# Adafruit_2_2_SPI_240x320.net
KiCad netlist of a schematic drawn in EAGLE
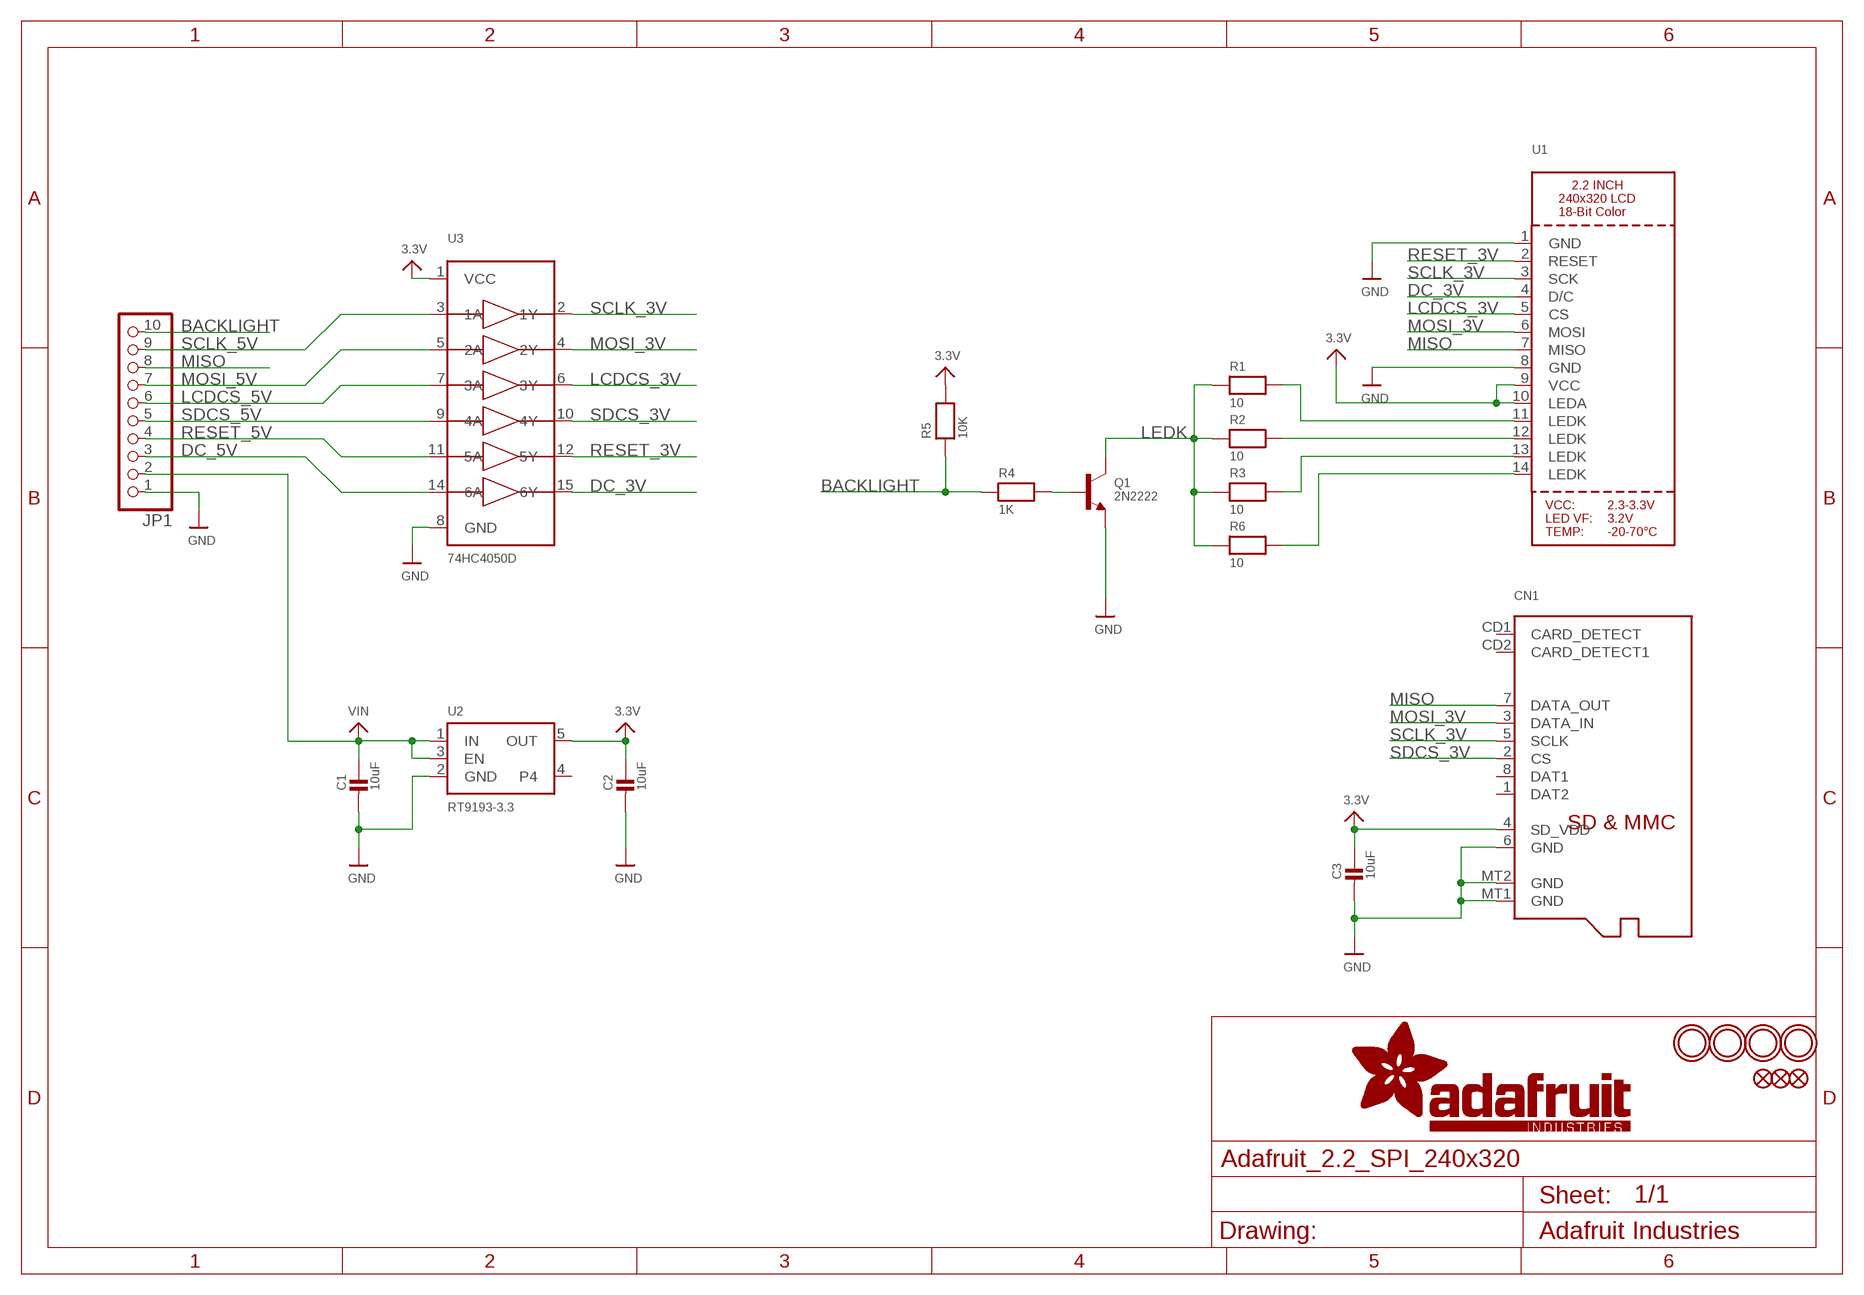
[diagram p0: schematic, sheet 1]

(export (version "E")
  (design (tool "Eeschema 10.0.6"))
  (components
    (comp (ref "C1")
      (value "10uF")
      (footprint "eagle-import:_0805MP")
      (libsource (lib "eagle-import") (part "CAP_CERAMIC_0805MP"))
    )
    (comp (ref "C2")
      (value "10uF")
      (footprint "eagle-import:_0805MP")
      (libsource (lib "eagle-import") (part "CAP_CERAMIC_0805MP"))
    )
    (comp (ref "C3")
      (value "10uF")
      (footprint "eagle-import:_0805MP")
      (libsource (lib "eagle-import") (part "CAP_CERAMIC_0805MP"))
    )
    (comp (ref "CN1")
      (value "MICROSD")
      (footprint "eagle-import:MICROSD")
      (libsource (lib "eagle-import") (part "MICROSD"))
    )
    (comp (ref "FID1")
      (value "FIDUCIAL\"\"")
      (footprint "eagle-import:FIDUCIAL_1MM")
      (libsource (lib "eagle-import") (part "FIDUCIAL{dblquote}{dblquote}"))
    )
    (comp (ref "FID2")
      (value "FIDUCIAL\"\"")
      (footprint "eagle-import:FIDUCIAL_1MM")
      (libsource (lib "eagle-import") (part "FIDUCIAL{dblquote}{dblquote}"))
    )
    (comp (ref "FID3")
      (value "FIDUCIAL\"\"")
      (footprint "eagle-import:FIDUCIAL_1MM")
      (fields (field (name "BOM") "EXCLUDE"))
      (libsource (lib "eagle-import") (part "FIDUCIAL{dblquote}{dblquote}"))
    )
    (comp (ref "JP1")
      (value "HEADER-1X1070MIL")
      (footprint "eagle-import:1X10_ROUND70")
      (libsource (lib "eagle-import") (part "HEADER-1X1070MIL"))
    )
    (comp (ref "Q1")
      (value "2N2222")
      (footprint "eagle-import:SOT23-WIDE")
      (libsource (lib "eagle-import") (part "TRANSISTOR_NPNWIDE"))
    )
    (comp (ref "R1")
      (value "10")
      (footprint "eagle-import:_0805MP")
      (libsource (lib "eagle-import") (part "RESISTOR_0805MP"))
    )
    (comp (ref "R2")
      (value "10")
      (footprint "eagle-import:_0805MP")
      (libsource (lib "eagle-import") (part "RESISTOR_0805MP"))
    )
    (comp (ref "R3")
      (value "10")
      (footprint "eagle-import:_0805MP")
      (libsource (lib "eagle-import") (part "RESISTOR_0805MP"))
    )
    (comp (ref "R4")
      (value "1K")
      (footprint "eagle-import:_0805MP")
      (libsource (lib "eagle-import") (part "RESISTOR_0805MP"))
    )
    (comp (ref "R5")
      (value "10K")
      (footprint "eagle-import:_0805MP")
      (libsource (lib "eagle-import") (part "RESISTOR_0805MP"))
    )
    (comp (ref "R6")
      (value "10")
      (footprint "eagle-import:_0805MP")
      (libsource (lib "eagle-import") (part "RESISTOR_0805MP"))
    )
    (comp (ref "U$2")
      (value "MOUNTINGHOLE2.5")
      (footprint "eagle-import:MOUNTINGHOLE_2.5_PLATED")
      (libsource (lib "eagle-import") (part "MOUNTINGHOLE2.5"))
    )
    (comp (ref "U$3")
      (value "MOUNTINGHOLE2.5")
      (footprint "eagle-import:MOUNTINGHOLE_2.5_PLATED")
      (libsource (lib "eagle-import") (part "MOUNTINGHOLE2.5"))
    )
    (comp (ref "U$4")
      (value "MOUNTINGHOLE2.5")
      (footprint "eagle-import:MOUNTINGHOLE_2.5_PLATED")
      (libsource (lib "eagle-import") (part "MOUNTINGHOLE2.5"))
    )
    (comp (ref "U$5")
      (value "MOUNTINGHOLE2.5")
      (footprint "eagle-import:MOUNTINGHOLE_2.5_PLATED")
      (libsource (lib "eagle-import") (part "MOUNTINGHOLE2.5"))
    )
    (comp (ref "U1")
      (value "DISP_LCD_TM022HDH26")
      (footprint "eagle-import:TM022HDH26_2.2IN_LCD")
      (libsource (lib "eagle-import") (part "DISP_LCD_TM022HDH26"))
    )
    (comp (ref "U2")
      (value "RT9193-3.3")
      (footprint "eagle-import:SOT23-5")
      (libsource (lib "eagle-import") (part "VREG_SOT23-5"))
    )
    (comp (ref "U3")
      (value "74HC4050D")
      (footprint "eagle-import:SOIC16")
      (libsource (lib "eagle-import") (part "74HC4050D"))
    )
  )
  (nets
    (net (code "1") (name "/BACKLIGHT") (class "Default")
      (node (ref "JP1") (pin "10") (pinfunction "10_10") (pintype "passive"))
      (node (ref "R4") (pin "1") (pinfunction "1_1") (pintype "passive"))
      (node (ref "R5") (pin "1") (pinfunction "1_1") (pintype "passive"))
    )
    (net (code "2") (name "/DC_3V") (class "Default")
      (node (ref "U1") (pin "4") (pinfunction "D/C_4") (pintype "input"))
      (node (ref "U3") (pin "15") (pinfunction "6Y_15") (pintype "bidirectional"))
    )
    (net (code "3") (name "/DC_5V") (class "Default")
      (node (ref "JP1") (pin "3") (pinfunction "3_3") (pintype "passive"))
      (node (ref "U3") (pin "14") (pinfunction "6A_14") (pintype "bidirectional"))
    )
    (net (code "4") (name "/LCDCS_3V") (class "Default")
      (node (ref "U1") (pin "5") (pinfunction "CS_5") (pintype "input"))
      (node (ref "U3") (pin "6") (pinfunction "3Y_6") (pintype "bidirectional"))
    )
    (net (code "5") (name "/LCDCS_5V") (class "Default")
      (node (ref "JP1") (pin "6") (pinfunction "6_6") (pintype "passive"))
      (node (ref "U3") (pin "7") (pinfunction "3A_7") (pintype "bidirectional"))
    )
    (net (code "6") (name "/LEDK") (class "Default")
      (node (ref "Q1") (pin "3") (pinfunction "C_3") (pintype "passive"))
      (node (ref "R1") (pin "1") (pinfunction "1_1") (pintype "passive"))
      (node (ref "R2") (pin "1") (pinfunction "1_1") (pintype "passive"))
      (node (ref "R3") (pin "1") (pinfunction "1_1") (pintype "passive"))
      (node (ref "R6") (pin "1") (pinfunction "1_1") (pintype "passive"))
    )
    (net (code "7") (name "/MISO") (class "Default")
      (node (ref "CN1") (pin "7") (pinfunction "DATA_OUT_7") (pintype "output"))
      (node (ref "JP1") (pin "8") (pinfunction "8_8") (pintype "passive"))
      (node (ref "U1") (pin "7") (pinfunction "MISO_7") (pintype "output"))
    )
    (net (code "8") (name "/MOSI_3V") (class "Default")
      (node (ref "CN1") (pin "3") (pinfunction "DATA_IN_3") (pintype "input"))
      (node (ref "U1") (pin "6") (pinfunction "MOSI_6") (pintype "input"))
      (node (ref "U3") (pin "4") (pinfunction "2Y_4") (pintype "bidirectional"))
    )
    (net (code "9") (name "/MOSI_5V") (class "Default")
      (node (ref "JP1") (pin "7") (pinfunction "7_7") (pintype "passive"))
      (node (ref "U3") (pin "5") (pinfunction "2A_5") (pintype "bidirectional"))
    )
    (net (code "10") (name "/RESET_3V") (class "Default")
      (node (ref "U1") (pin "2") (pinfunction "RESET_2") (pintype "input"))
      (node (ref "U3") (pin "12") (pinfunction "5Y_12") (pintype "bidirectional"))
    )
    (net (code "11") (name "/RESET_5V") (class "Default")
      (node (ref "JP1") (pin "4") (pinfunction "4_4") (pintype "passive"))
      (node (ref "U3") (pin "11") (pinfunction "5A_11") (pintype "bidirectional"))
    )
    (net (code "12") (name "/SCLK_3V") (class "Default")
      (node (ref "CN1") (pin "5") (pinfunction "SCLK_5") (pintype "input"))
      (node (ref "U1") (pin "3") (pinfunction "SCK_3") (pintype "input"))
      (node (ref "U3") (pin "2") (pinfunction "1Y_2") (pintype "bidirectional"))
    )
    (net (code "13") (name "/SCLK_5V") (class "Default")
      (node (ref "JP1") (pin "9") (pinfunction "9_9") (pintype "passive"))
      (node (ref "U3") (pin "3") (pinfunction "1A_3") (pintype "bidirectional"))
    )
    (net (code "14") (name "/SDCS_3V") (class "Default")
      (node (ref "CN1") (pin "2") (pinfunction "CS_2") (pintype "input"))
      (node (ref "U3") (pin "10") (pinfunction "4Y_10") (pintype "bidirectional"))
    )
    (net (code "15") (name "/SDCS_5V") (class "Default")
      (node (ref "JP1") (pin "5") (pinfunction "5_5") (pintype "passive"))
      (node (ref "U3") (pin "9") (pinfunction "4A_9") (pintype "bidirectional"))
    )
    (net (code "16") (name "3.3V") (class "Default")
      (node (ref "C2") (pin "1") (pinfunction "1_1") (pintype "passive"))
      (node (ref "C3") (pin "1") (pinfunction "1_1") (pintype "passive"))
      (node (ref "CN1") (pin "4") (pinfunction "SD_VDD_4") (pintype "power_in"))
      (node (ref "R5") (pin "2") (pinfunction "2_2") (pintype "passive"))
      (node (ref "U1") (pin "10") (pinfunction "LEDA_10") (pintype "power_in"))
      (node (ref "U1") (pin "9") (pinfunction "VCC_9") (pintype "power_in"))
      (node (ref "U2") (pin "5") (pinfunction "OUT_5") (pintype "power_in"))
      (node (ref "U3") (pin "1") (pinfunction "VCC_1") (pintype "bidirectional"))
    )
    (net (code "17") (name "GND") (class "Default")
      (node (ref "C1") (pin "2") (pinfunction "2_2") (pintype "passive"))
      (node (ref "C2") (pin "2") (pinfunction "2_2") (pintype "passive"))
      (node (ref "C3") (pin "2") (pinfunction "2_2") (pintype "passive"))
      (node (ref "CN1") (pin "6") (pinfunction "GND_6") (pintype "power_in"))
      (node (ref "CN1") (pin "MT1") (pinfunction "GND_MT1") (pintype "power_in"))
      (node (ref "CN1") (pin "MT2") (pinfunction "GND_MT2") (pintype "power_in"))
      (node (ref "JP1") (pin "1") (pinfunction "1_1") (pintype "passive"))
      (node (ref "Q1") (pin "2") (pinfunction "E_2") (pintype "passive"))
      (node (ref "U1") (pin "1") (pinfunction "GND_1") (pintype "power_in"))
      (node (ref "U1") (pin "8") (pinfunction "GND_8") (pintype "power_in"))
      (node (ref "U2") (pin "2") (pinfunction "GND_2") (pintype "power_in"))
      (node (ref "U3") (pin "8") (pinfunction "GND_8") (pintype "bidirectional"))
    )
    (net (code "18") (name "Net-(Q1-B)") (class "Default")
      (node (ref "Q1") (pin "1") (pinfunction "B_1") (pintype "passive"))
      (node (ref "R4") (pin "2") (pinfunction "2_2") (pintype "passive"))
    )
    (net (code "19") (name "Net-(R1-Pad2)") (class "Default")
      (node (ref "R1") (pin "2") (pinfunction "2_2") (pintype "passive"))
      (node (ref "U1") (pin "11") (pinfunction "LEDK_11") (pintype "power_in"))
    )
    (net (code "20") (name "Net-(R2-Pad2)") (class "Default")
      (node (ref "R2") (pin "2") (pinfunction "2_2") (pintype "passive"))
      (node (ref "U1") (pin "12") (pinfunction "LEDK_12") (pintype "power_in"))
    )
    (net (code "21") (name "Net-(R3-Pad2)") (class "Default")
      (node (ref "R3") (pin "2") (pinfunction "2_2") (pintype "passive"))
      (node (ref "U1") (pin "13") (pinfunction "LEDK_13") (pintype "power_in"))
    )
    (net (code "22") (name "Net-(R6-Pad2)") (class "Default")
      (node (ref "R6") (pin "2") (pinfunction "2_2") (pintype "passive"))
      (node (ref "U1") (pin "14") (pinfunction "LEDK_14") (pintype "power_in"))
    )
    (net (code "23") (name "VIN") (class "Default")
      (node (ref "C1") (pin "1") (pinfunction "1_1") (pintype "passive"))
      (node (ref "JP1") (pin "2") (pinfunction "2_2") (pintype "passive"))
      (node (ref "U2") (pin "1") (pinfunction "IN_1") (pintype "power_in"))
      (node (ref "U2") (pin "3") (pinfunction "EN_3") (pintype "input"))
    )
    (net (code "24") (name "unconnected-(CN1-CARD_DETECT-PadCD1)") (class "Default")
      (node (ref "CN1") (pin "CD1") (pinfunction "CARD_DETECT_CD1") (pintype "passive"))
    )
    (net (code "25") (name "unconnected-(CN1-CARD_DETECT1-PadCD2)") (class "Default")
      (node (ref "CN1") (pin "CD2") (pinfunction "CARD_DETECT1_CD2") (pintype "passive"))
    )
    (net (code "26") (name "unconnected-(CN1-DAT1-Pad8)") (class "Default")
      (node (ref "CN1") (pin "8") (pinfunction "DAT1_8") (pintype "bidirectional"))
    )
    (net (code "27") (name "unconnected-(CN1-DAT2-Pad1)") (class "Default")
      (node (ref "CN1") (pin "1") (pinfunction "DAT2_1") (pintype "bidirectional"))
    )
    (net (code "28") (name "unconnected-(U2-P4-Pad4)") (class "Default")
      (node (ref "U2") (pin "4") (pinfunction "P4_4") (pintype "bidirectional"))
    )
  )
)
